# PAYL0005_PC_Microcontroller_Power.net
KiCad netlist of a schematic drawn in Altium Designer
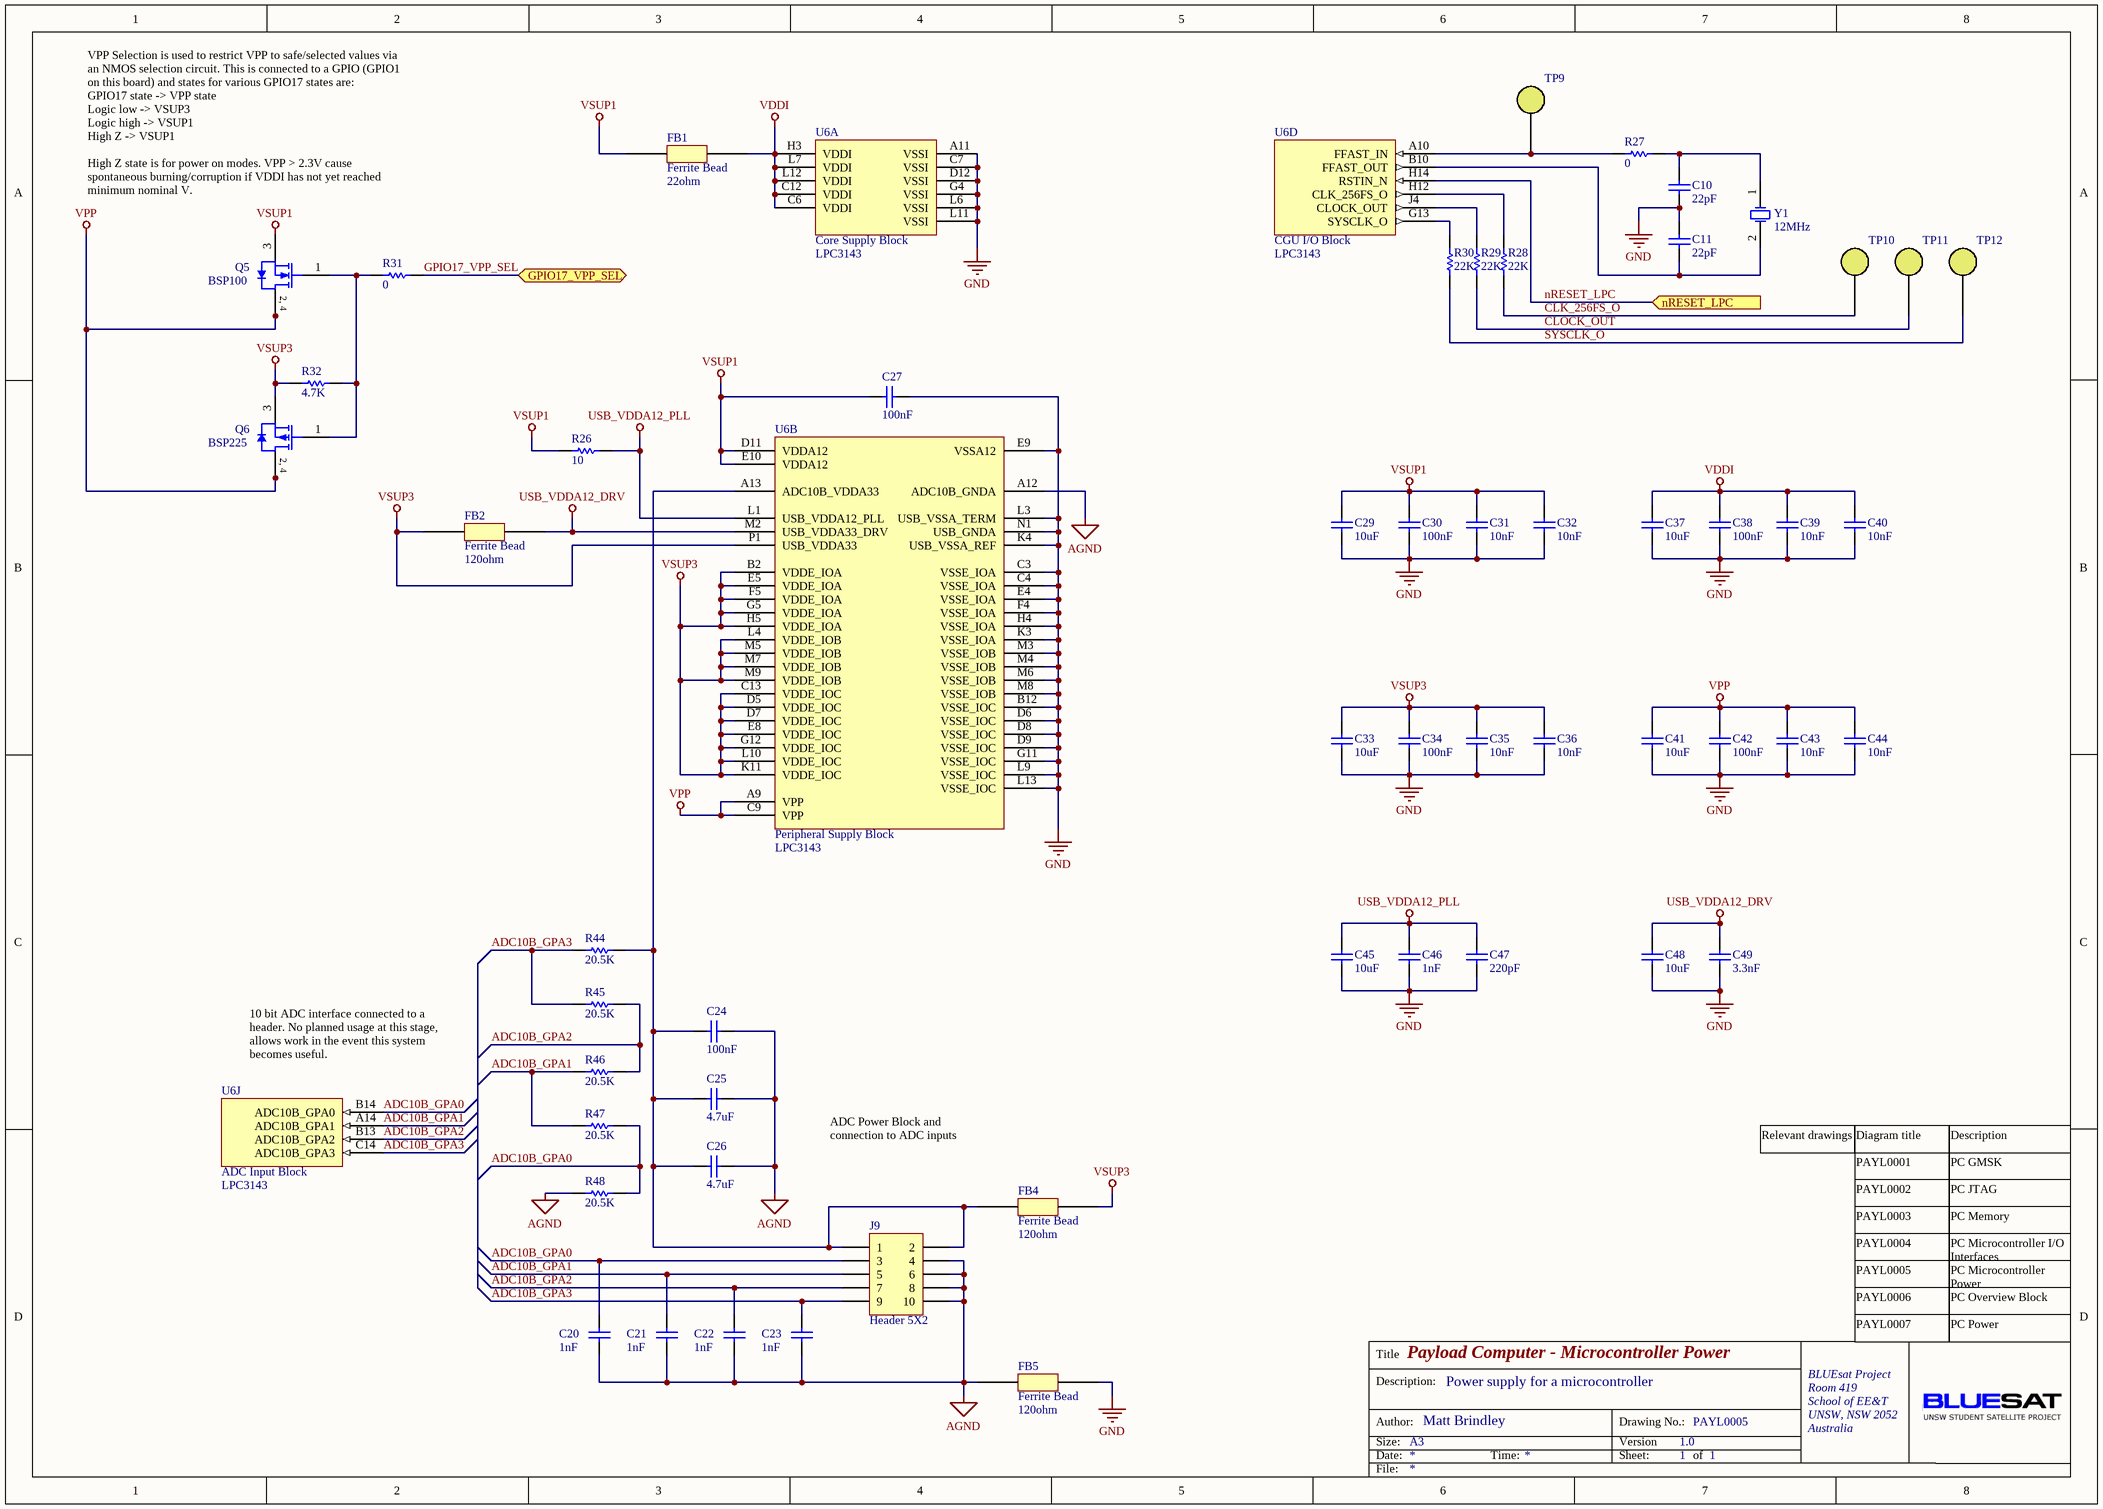
[diagram p0: PAYL0005_PC_Microcontroller_Power.SchDoc]

(export (version "E")
  (design (tool "Eeschema 10.0.6"))
  (components
    (comp (ref "C10")
      (value "22pF")
      (footprint "C0805")
      (description "Capacitor (Semiconductor SIM Model)")
      (fields (field (name "Comment") "Cap Semi") (field (name "PUBLISHER") "Altium Limited"))
      (libsource (lib "Miscellaneous Devices") (part "Cap Semi"))
    )
    (comp (ref "C11")
      (value "22pF")
      (footprint "C0805")
      (description "Capacitor (Semiconductor SIM Model)")
      (fields (field (name "Comment") "Cap Semi") (field (name "PUBLISHER") "Altium Limited"))
      (libsource (lib "Miscellaneous Devices") (part "Cap Semi"))
    )
    (comp (ref "C20")
      (value "1nF")
      (footprint "C0805")
      (description "Capacitor (Semiconductor SIM Model)")
      (fields (field (name "Comment") "Cap Semi") (field (name "PUBLISHER") "Altium Limited"))
      (libsource (lib "Miscellaneous Devices") (part "Cap Semi"))
    )
    (comp (ref "C21")
      (value "1nF")
      (footprint "C0805")
      (description "Capacitor (Semiconductor SIM Model)")
      (fields (field (name "Comment") "Cap Semi") (field (name "PUBLISHER") "Altium Limited"))
      (libsource (lib "Miscellaneous Devices") (part "Cap Semi"))
    )
    (comp (ref "C22")
      (value "1nF")
      (footprint "C0805")
      (description "Capacitor (Semiconductor SIM Model)")
      (fields (field (name "Comment") "Cap Semi") (field (name "PUBLISHER") "Altium Limited"))
      (libsource (lib "Miscellaneous Devices") (part "Cap Semi"))
    )
    (comp (ref "C23")
      (value "1nF")
      (footprint "C0805")
      (description "Capacitor (Semiconductor SIM Model)")
      (fields (field (name "Comment") "Cap Semi") (field (name "PUBLISHER") "Altium Limited"))
      (libsource (lib "Miscellaneous Devices") (part "Cap Semi"))
    )
    (comp (ref "C24")
      (value "100nF")
      (footprint "C0805")
      (description "Capacitor (Semiconductor SIM Model)")
      (fields (field (name "Comment") "Cap Semi") (field (name "PUBLISHER") "Altium Limited"))
      (libsource (lib "Miscellaneous Devices") (part "Cap Semi"))
    )
    (comp (ref "C25")
      (value "4.7uF")
      (footprint "C0805")
      (description "Capacitor (Semiconductor SIM Model)")
      (fields (field (name "Comment") "Cap Semi") (field (name "PUBLISHER") "Altium Limited"))
      (libsource (lib "Miscellaneous Devices") (part "Cap Semi"))
    )
    (comp (ref "C26")
      (value "4.7uF")
      (footprint "C0805")
      (description "Capacitor (Semiconductor SIM Model)")
      (fields (field (name "Comment") "Cap Semi") (field (name "PUBLISHER") "Altium Limited"))
      (libsource (lib "Miscellaneous Devices") (part "Cap Semi"))
    )
    (comp (ref "C27")
      (value "100nF")
      (footprint "C0805")
      (description "Capacitor (Semiconductor SIM Model)")
      (fields (field (name "Comment") "Cap Semi") (field (name "PUBLISHER") "Altium Limited"))
      (libsource (lib "Miscellaneous Devices") (part "Cap Semi"))
    )
    (comp (ref "C29")
      (value "10uF")
      (footprint "C0805")
      (description "Capacitor (Semiconductor SIM Model)")
      (fields (field (name "Comment") "Cap Semi") (field (name "PUBLISHER") "Altium Limited"))
      (libsource (lib "Miscellaneous Devices") (part "Cap Semi"))
    )
    (comp (ref "C30")
      (value "100nF")
      (footprint "C0805")
      (description "Capacitor (Semiconductor SIM Model)")
      (fields (field (name "Comment") "Cap Semi") (field (name "PUBLISHER") "Altium Limited"))
      (libsource (lib "Miscellaneous Devices") (part "Cap Semi"))
    )
    (comp (ref "C31")
      (value "10nF")
      (footprint "C0805")
      (description "Capacitor (Semiconductor SIM Model)")
      (fields (field (name "Comment") "Cap Semi") (field (name "PUBLISHER") "Altium Limited"))
      (libsource (lib "Miscellaneous Devices") (part "Cap Semi"))
    )
    (comp (ref "C32")
      (value "10nF")
      (footprint "C0805")
      (description "Capacitor (Semiconductor SIM Model)")
      (fields (field (name "Comment") "Cap Semi") (field (name "PUBLISHER") "Altium Limited"))
      (libsource (lib "Miscellaneous Devices") (part "Cap Semi"))
    )
    (comp (ref "C33")
      (value "10uF")
      (footprint "C0805")
      (description "Capacitor (Semiconductor SIM Model)")
      (fields (field (name "Comment") "Cap Semi") (field (name "PUBLISHER") "Altium Limited"))
      (libsource (lib "Miscellaneous Devices") (part "Cap Semi"))
    )
    (comp (ref "C34")
      (value "100nF")
      (footprint "C0805")
      (description "Capacitor (Semiconductor SIM Model)")
      (fields (field (name "Comment") "Cap Semi") (field (name "PUBLISHER") "Altium Limited"))
      (libsource (lib "Miscellaneous Devices") (part "Cap Semi"))
    )
    (comp (ref "C35")
      (value "10nF")
      (footprint "C0805")
      (description "Capacitor (Semiconductor SIM Model)")
      (fields (field (name "Comment") "Cap Semi") (field (name "PUBLISHER") "Altium Limited"))
      (libsource (lib "Miscellaneous Devices") (part "Cap Semi"))
    )
    (comp (ref "C36")
      (value "10nF")
      (footprint "C0805")
      (description "Capacitor (Semiconductor SIM Model)")
      (fields (field (name "Comment") "Cap Semi") (field (name "PUBLISHER") "Altium Limited"))
      (libsource (lib "Miscellaneous Devices") (part "Cap Semi"))
    )
    (comp (ref "C37")
      (value "10uF")
      (footprint "C0805")
      (description "Capacitor (Semiconductor SIM Model)")
      (fields (field (name "Comment") "Cap Semi") (field (name "PUBLISHER") "Altium Limited"))
      (libsource (lib "Miscellaneous Devices") (part "Cap Semi"))
    )
    (comp (ref "C38")
      (value "100nF")
      (footprint "C0805")
      (description "Capacitor (Semiconductor SIM Model)")
      (fields (field (name "Comment") "Cap Semi") (field (name "PUBLISHER") "Altium Limited"))
      (libsource (lib "Miscellaneous Devices") (part "Cap Semi"))
    )
    (comp (ref "C39")
      (value "10nF")
      (footprint "C0805")
      (description "Capacitor (Semiconductor SIM Model)")
      (fields (field (name "Comment") "Cap Semi") (field (name "PUBLISHER") "Altium Limited"))
      (libsource (lib "Miscellaneous Devices") (part "Cap Semi"))
    )
    (comp (ref "C40")
      (value "10nF")
      (footprint "C0805")
      (description "Capacitor (Semiconductor SIM Model)")
      (fields (field (name "Comment") "Cap Semi") (field (name "PUBLISHER") "Altium Limited"))
      (libsource (lib "Miscellaneous Devices") (part "Cap Semi"))
    )
    (comp (ref "C41")
      (value "10uF")
      (footprint "C0805")
      (description "Capacitor (Semiconductor SIM Model)")
      (fields (field (name "Comment") "Cap Semi") (field (name "PUBLISHER") "Altium Limited"))
      (libsource (lib "Miscellaneous Devices") (part "Cap Semi"))
    )
    (comp (ref "C42")
      (value "100nF")
      (footprint "C0805")
      (description "Capacitor (Semiconductor SIM Model)")
      (fields (field (name "Comment") "Cap Semi") (field (name "PUBLISHER") "Altium Limited"))
      (libsource (lib "Miscellaneous Devices") (part "Cap Semi"))
    )
    (comp (ref "C43")
      (value "10nF")
      (footprint "C0805")
      (description "Capacitor (Semiconductor SIM Model)")
      (fields (field (name "Comment") "Cap Semi") (field (name "PUBLISHER") "Altium Limited"))
      (libsource (lib "Miscellaneous Devices") (part "Cap Semi"))
    )
    (comp (ref "C44")
      (value "10nF")
      (footprint "C0805")
      (description "Capacitor (Semiconductor SIM Model)")
      (fields (field (name "Comment") "Cap Semi") (field (name "PUBLISHER") "Altium Limited"))
      (libsource (lib "Miscellaneous Devices") (part "Cap Semi"))
    )
    (comp (ref "C45")
      (value "10uF")
      (footprint "C0805")
      (description "Capacitor (Semiconductor SIM Model)")
      (fields (field (name "Comment") "Cap Semi") (field (name "PUBLISHER") "Altium Limited"))
      (libsource (lib "Miscellaneous Devices") (part "Cap Semi"))
    )
    (comp (ref "C46")
      (value "1nF")
      (footprint "C0805")
      (description "Capacitor (Semiconductor SIM Model)")
      (fields (field (name "Comment") "Cap Semi") (field (name "PUBLISHER") "Altium Limited"))
      (libsource (lib "Miscellaneous Devices") (part "Cap Semi"))
    )
    (comp (ref "C47")
      (value "220pF")
      (footprint "C0805")
      (description "Capacitor (Semiconductor SIM Model)")
      (fields (field (name "Comment") "Cap Semi") (field (name "PUBLISHER") "Altium Limited"))
      (libsource (lib "Miscellaneous Devices") (part "Cap Semi"))
    )
    (comp (ref "C48")
      (value "10uF")
      (footprint "C0805")
      (description "Capacitor (Semiconductor SIM Model)")
      (fields (field (name "Comment") "Cap Semi") (field (name "PUBLISHER") "Altium Limited"))
      (libsource (lib "Miscellaneous Devices") (part "Cap Semi"))
    )
    (comp (ref "C49")
      (value "3.3nF")
      (footprint "C0805")
      (description "Capacitor (Semiconductor SIM Model)")
      (fields (field (name "Comment") "Cap Semi") (field (name "PUBLISHER") "Altium Limited"))
      (libsource (lib "Miscellaneous Devices") (part "Cap Semi"))
    )
    (comp (ref "FB1")
      (value "Ferrite Bead")
      (footprint "AXIAL-0.3")
      (description "Standard Ferrite Bead")
      (fields (field (name "ALTIUM_VALUE") "22ohm") (field (name "PUBLISHER") "Altium Limited"))
      (libsource (lib "PC_Components") (part "Ferrite Bead"))
    )
    (comp (ref "FB2")
      (value "Ferrite Bead")
      (footprint "AXIAL-0.3")
      (description "Standard Ferrite Bead")
      (fields (field (name "ALTIUM_VALUE") "120ohm") (field (name "PUBLISHER") "Altium Limited"))
      (libsource (lib "PC_Components") (part "Ferrite Bead"))
    )
    (comp (ref "FB4")
      (value "Ferrite Bead")
      (footprint "AXIAL-0.3")
      (description "Standard Ferrite Bead")
      (fields (field (name "ALTIUM_VALUE") "120ohm") (field (name "PUBLISHER") "Altium Limited"))
      (libsource (lib "PC_Components") (part "Ferrite Bead"))
    )
    (comp (ref "FB5")
      (value "Ferrite Bead")
      (footprint "AXIAL-0.3")
      (description "Standard Ferrite Bead")
      (fields (field (name "ALTIUM_VALUE") "120ohm") (field (name "PUBLISHER") "Altium Limited"))
      (libsource (lib "PC_Components") (part "Ferrite Bead"))
    )
    (comp (ref "J9")
      (value "Header 5X2")
      (footprint "HDR2X5")
      (description "Header, 5-Pin, Dual row")
      (fields (field (name "PUBLISHER") "Altium Limited"))
      (libsource (lib "Miscellaneous Connectors") (part "Header 5X2"))
    )
    (comp (ref "Q5")
      (value "BSP100")
      (footprint "SOT223_N")
      (description "N-channel Enhancement Mode MOSFET")
      (fields (field (name "PUBLISHER") "Altium Limited"))
      (libsource (lib "Philips Discrete MOSFET - Power") (part "BSP100"))
    )
    (comp (ref "Q6")
      (value "BSP225")
      (footprint "SOT223_N")
      (description "P-channel Enhancement Mode Vertical D-MOSFET")
      (fields (field (name "PUBLISHER") "Altium Limited"))
      (libsource (lib "Philips Discrete MOSFET - Power") (part "BSP225"))
    )
    (comp (ref "R26")
      (value "10")
      (footprint "6-0805_L")
      (description "Semiconductor Resistor")
      (fields (field (name "Comment") "Res Semi") (field (name "PUBLISHER") "Altium Limited"))
      (libsource (lib "Miscellaneous Devices") (part "Res Semi"))
    )
    (comp (ref "R27")
      (value "0")
      (footprint "6-0805_L")
      (description "Semiconductor Resistor")
      (fields (field (name "Comment") "Res Semi") (field (name "PUBLISHER") "Altium Limited"))
      (libsource (lib "Miscellaneous Devices") (part "Res Semi"))
    )
    (comp (ref "R28")
      (value "22K")
      (footprint "6-0805_L")
      (description "Semiconductor Resistor")
      (fields (field (name "Comment") "Res Semi") (field (name "PUBLISHER") "Altium Limited"))
      (libsource (lib "Miscellaneous Devices") (part "Res Semi"))
    )
    (comp (ref "R29")
      (value "22K")
      (footprint "6-0805_L")
      (description "Semiconductor Resistor")
      (fields (field (name "Comment") "Res Semi") (field (name "PUBLISHER") "Altium Limited"))
      (libsource (lib "Miscellaneous Devices") (part "Res Semi"))
    )
    (comp (ref "R30")
      (value "22K")
      (footprint "6-0805_L")
      (description "Semiconductor Resistor")
      (fields (field (name "Comment") "Res Semi") (field (name "PUBLISHER") "Altium Limited"))
      (libsource (lib "Miscellaneous Devices") (part "Res Semi"))
    )
    (comp (ref "R31")
      (value "0")
      (footprint "6-0805_L")
      (description "Semiconductor Resistor")
      (fields (field (name "Comment") "Res Semi") (field (name "PUBLISHER") "Altium Limited"))
      (libsource (lib "Miscellaneous Devices") (part "Res Semi"))
    )
    (comp (ref "R32")
      (value "4.7K")
      (footprint "6-0805_L")
      (description "Semiconductor Resistor")
      (fields (field (name "Comment") "Res Semi") (field (name "PUBLISHER") "Altium Limited"))
      (libsource (lib "Miscellaneous Devices") (part "Res Semi"))
    )
    (comp (ref "R44")
      (value "20.5K")
      (footprint "6-0805_L")
      (description "Semiconductor Resistor")
      (fields (field (name "Comment") "Res Semi") (field (name "PUBLISHER") "Altium Limited"))
      (libsource (lib "Miscellaneous Devices") (part "Res Semi"))
    )
    (comp (ref "R45")
      (value "20.5K")
      (footprint "6-0805_L")
      (description "Semiconductor Resistor")
      (fields (field (name "Comment") "Res Semi") (field (name "PUBLISHER") "Altium Limited"))
      (libsource (lib "Miscellaneous Devices") (part "Res Semi"))
    )
    (comp (ref "R46")
      (value "20.5K")
      (footprint "6-0805_L")
      (description "Semiconductor Resistor")
      (fields (field (name "Comment") "Res Semi") (field (name "PUBLISHER") "Altium Limited"))
      (libsource (lib "Miscellaneous Devices") (part "Res Semi"))
    )
    (comp (ref "R47")
      (value "20.5K")
      (footprint "6-0805_L")
      (description "Semiconductor Resistor")
      (fields (field (name "Comment") "Res Semi") (field (name "PUBLISHER") "Altium Limited"))
      (libsource (lib "Miscellaneous Devices") (part "Res Semi"))
    )
    (comp (ref "R48")
      (value "20.5K")
      (footprint "6-0805_L")
      (description "Semiconductor Resistor")
      (fields (field (name "Comment") "Res Semi") (field (name "PUBLISHER") "Altium Limited"))
      (libsource (lib "Miscellaneous Devices") (part "Res Semi"))
    )
    (comp (ref "TP9")
      (value "Test Point")
      (footprint "PIN1")
      (description "Test point")
      (fields (field (name "PUBLISHER") "Altium Limited"))
      (libsource (lib "PC_Components") (part "Test Point"))
    )
    (comp (ref "TP10")
      (value "Test Point")
      (footprint "PIN1")
      (description "Test point")
      (fields (field (name "PUBLISHER") "Altium Limited"))
      (libsource (lib "PC_Components") (part "Test Point"))
    )
    (comp (ref "TP11")
      (value "Test Point")
      (footprint "PIN1")
      (description "Test point")
      (fields (field (name "PUBLISHER") "Altium Limited"))
      (libsource (lib "PC_Components") (part "Test Point"))
    )
    (comp (ref "TP12")
      (value "Test Point")
      (footprint "PIN1")
      (description "Test point")
      (fields (field (name "PUBLISHER") "Altium Limited"))
      (libsource (lib "PC_Components") (part "Test Point"))
    )
    (comp (ref "U6")
      (value "LPC3143")
      (footprint "PC_Footprints:BGA180C80P14X14_1200X1200X120")
      (description "NXP ARM9 based microcontroller")
      (fields (field (name "PUBLISHER") "BLUEsat Project"))
      (libsource (lib "PC_Components") (part "LPC3143"))
    )
    (comp (ref "Y1")
      (value "12MHz")
      (footprint "RAD-0.3")
      (description "Crystal Oscillator")
      (fields (field (name "Comment") "XTAL") (field (name "PUBLISHER") "Altium Limited"))
      (libsource (lib "Miscellaneous Devices") (part "XTAL"))
    )
  )
  (nets
    (net (code "1") (name "/ADC10B_GPA0") (class "Default")
      (node (ref "C20") (pin "2") (pinfunction "2_2") (pintype "passive"))
      (node (ref "J9") (pin "3") (pinfunction "3_3") (pintype "passive"))
      (node (ref "R47") (pin "2") (pinfunction "2_2") (pintype "passive"))
      (node (ref "R48") (pin "2") (pinfunction "2_2") (pintype "passive"))
      (node (ref "U6") (pin "B14") (pinfunction "ADC10B_GPA0_B14") (pintype "input"))
    )
    (net (code "2") (name "/ADC10B_GPA1") (class "Default")
      (node (ref "C21") (pin "2") (pinfunction "2_2") (pintype "passive"))
      (node (ref "J9") (pin "5") (pinfunction "5_5") (pintype "passive"))
      (node (ref "R46") (pin "1") (pinfunction "1_1") (pintype "passive"))
      (node (ref "R47") (pin "1") (pinfunction "1_1") (pintype "passive"))
      (node (ref "U6") (pin "A14") (pinfunction "ADC10B_GPA1_A14") (pintype "input"))
    )
    (net (code "3") (name "/ADC10B_GPA2") (class "Default")
      (node (ref "C22") (pin "2") (pinfunction "2_2") (pintype "passive"))
      (node (ref "J9") (pin "7") (pinfunction "7_7") (pintype "passive"))
      (node (ref "R45") (pin "2") (pinfunction "2_2") (pintype "passive"))
      (node (ref "R46") (pin "2") (pinfunction "2_2") (pintype "passive"))
      (node (ref "U6") (pin "B13") (pinfunction "ADC10B_GPA2_B13") (pintype "input"))
    )
    (net (code "4") (name "/ADC10B_GPA3") (class "Default")
      (node (ref "C23") (pin "2") (pinfunction "2_2") (pintype "passive"))
      (node (ref "J9") (pin "9") (pinfunction "9_9") (pintype "passive"))
      (node (ref "R44") (pin "1") (pinfunction "1_1") (pintype "passive"))
      (node (ref "R45") (pin "1") (pinfunction "1_1") (pintype "passive"))
      (node (ref "U6") (pin "C14") (pinfunction "ADC10B_GPA3_C14") (pintype "input"))
    )
    (net (code "5") (name "/CLK_256FS_O") (class "Default")
      (node (ref "R28") (pin "1") (pinfunction "1_1") (pintype "passive"))
      (node (ref "TP10") (pin "1") (pinfunction "1_1") (pintype "passive"))
    )
    (net (code "6") (name "/CLOCK_OUT") (class "Default")
      (node (ref "R29") (pin "1") (pinfunction "1_1") (pintype "passive"))
      (node (ref "TP11") (pin "1") (pinfunction "1_1") (pintype "passive"))
    )
    (net (code "7") (name "/GPIO17_VPP_SEL") (class "Default")
      (node (ref "R31") (pin "2") (pinfunction "2_2") (pintype "passive"))
    )
    (net (code "8") (name "/SYSCLK_O") (class "Default")
      (node (ref "R30") (pin "1") (pinfunction "1_1") (pintype "passive"))
      (node (ref "TP12") (pin "1") (pinfunction "1_1") (pintype "passive"))
    )
    (net (code "9") (name "/nRESET_LPC") (class "Default")
      (node (ref "U6") (pin "H14") (pinfunction "RSTIN_N_H14") (pintype "input"))
    )
    (net (code "10") (name "AGND") (class "Default")
      (node (ref "C20") (pin "1") (pinfunction "1_1") (pintype "passive"))
      (node (ref "C21") (pin "1") (pinfunction "1_1") (pintype "passive"))
      (node (ref "C22") (pin "1") (pinfunction "1_1") (pintype "passive"))
      (node (ref "C23") (pin "1") (pinfunction "1_1") (pintype "passive"))
      (node (ref "C24") (pin "1") (pinfunction "1_1") (pintype "passive"))
      (node (ref "C25") (pin "1") (pinfunction "1_1") (pintype "passive"))
      (node (ref "C26") (pin "1") (pinfunction "1_1") (pintype "passive"))
      (node (ref "FB5") (pin "2") (pinfunction "2_2") (pintype "passive"))
      (node (ref "J9") (pin "10") (pinfunction "10_10") (pintype "passive"))
      (node (ref "J9") (pin "4") (pinfunction "4_4") (pintype "passive"))
      (node (ref "J9") (pin "6") (pinfunction "6_6") (pintype "passive"))
      (node (ref "J9") (pin "8") (pinfunction "8_8") (pintype "passive"))
      (node (ref "R48") (pin "1") (pinfunction "1_1") (pintype "passive"))
      (node (ref "U6") (pin "A12") (pinfunction "ADC10B_GNDA_A12") (pintype "power_in"))
    )
    (net (code "11") (name "GND") (class "Default")
      (node (ref "C10") (pin "2") (pinfunction "2_2") (pintype "passive"))
      (node (ref "C11") (pin "1") (pinfunction "1_1") (pintype "passive"))
      (node (ref "C27") (pin "1") (pinfunction "1_1") (pintype "passive"))
      (node (ref "C29") (pin "2") (pinfunction "2_2") (pintype "passive"))
      (node (ref "C30") (pin "2") (pinfunction "2_2") (pintype "passive"))
      (node (ref "C31") (pin "2") (pinfunction "2_2") (pintype "passive"))
      (node (ref "C32") (pin "2") (pinfunction "2_2") (pintype "passive"))
      (node (ref "C33") (pin "2") (pinfunction "2_2") (pintype "passive"))
      (node (ref "C34") (pin "2") (pinfunction "2_2") (pintype "passive"))
      (node (ref "C35") (pin "2") (pinfunction "2_2") (pintype "passive"))
      (node (ref "C36") (pin "2") (pinfunction "2_2") (pintype "passive"))
      (node (ref "C37") (pin "2") (pinfunction "2_2") (pintype "passive"))
      (node (ref "C38") (pin "2") (pinfunction "2_2") (pintype "passive"))
      (node (ref "C39") (pin "2") (pinfunction "2_2") (pintype "passive"))
      (node (ref "C40") (pin "2") (pinfunction "2_2") (pintype "passive"))
      (node (ref "C41") (pin "2") (pinfunction "2_2") (pintype "passive"))
      (node (ref "C42") (pin "2") (pinfunction "2_2") (pintype "passive"))
      (node (ref "C43") (pin "2") (pinfunction "2_2") (pintype "passive"))
      (node (ref "C44") (pin "2") (pinfunction "2_2") (pintype "passive"))
      (node (ref "C45") (pin "2") (pinfunction "2_2") (pintype "passive"))
      (node (ref "C46") (pin "2") (pinfunction "2_2") (pintype "passive"))
      (node (ref "C47") (pin "2") (pinfunction "2_2") (pintype "passive"))
      (node (ref "C48") (pin "2") (pinfunction "2_2") (pintype "passive"))
      (node (ref "C49") (pin "2") (pinfunction "2_2") (pintype "passive"))
      (node (ref "FB5") (pin "1") (pinfunction "1_1") (pintype "passive"))
      (node (ref "U6") (pin "A11") (pinfunction "VSSI_A11") (pintype "power_in"))
      (node (ref "U6") (pin "B12") (pinfunction "VSSE_IOC_B12") (pintype "power_in"))
      (node (ref "U6") (pin "C3") (pinfunction "VSSE_IOA_C3") (pintype "power_in"))
      (node (ref "U6") (pin "C4") (pinfunction "VSSE_IOA_C4") (pintype "power_in"))
      (node (ref "U6") (pin "C7") (pinfunction "VSSI_C7") (pintype "power_in"))
      (node (ref "U6") (pin "D12") (pinfunction "VSSI_D12") (pintype "power_in"))
      (node (ref "U6") (pin "D6") (pinfunction "VSSE_IOC_D6") (pintype "power_in"))
      (node (ref "U6") (pin "D8") (pinfunction "VSSE_IOC_D8") (pintype "power_in"))
      (node (ref "U6") (pin "D9") (pinfunction "VSSE_IOC_D9") (pintype "power_in"))
      (node (ref "U6") (pin "E4") (pinfunction "VSSE_IOA_E4") (pintype "power_in"))
      (node (ref "U6") (pin "E9") (pinfunction "VSSA12_E9") (pintype "power_in"))
      (node (ref "U6") (pin "F4") (pinfunction "VSSE_IOA_F4") (pintype "power_in"))
      (node (ref "U6") (pin "G11") (pinfunction "VSSE_IOC_G11") (pintype "power_in"))
      (node (ref "U6") (pin "G4") (pinfunction "VSSI_G4") (pintype "power_in"))
      (node (ref "U6") (pin "H4") (pinfunction "VSSE_IOA_H4") (pintype "power_in"))
      (node (ref "U6") (pin "K3") (pinfunction "VSSE_IOA_K3") (pintype "power_in"))
      (node (ref "U6") (pin "K4") (pinfunction "USB_VSSA_REF_K4") (pintype "power_in"))
      (node (ref "U6") (pin "L11") (pinfunction "VSSI_L11") (pintype "power_in"))
      (node (ref "U6") (pin "L13") (pinfunction "VSSE_IOC_L13") (pintype "power_in"))
      (node (ref "U6") (pin "L3") (pinfunction "USB_VSSA_TERM_L3") (pintype "power_in"))
      (node (ref "U6") (pin "L6") (pinfunction "VSSI_L6") (pintype "power_in"))
      (node (ref "U6") (pin "L9") (pinfunction "VSSE_IOC_L9") (pintype "power_in"))
      (node (ref "U6") (pin "M3") (pinfunction "VSSE_IOB_M3") (pintype "power_in"))
      (node (ref "U6") (pin "M4") (pinfunction "VSSE_IOB_M4") (pintype "power_in"))
      (node (ref "U6") (pin "M6") (pinfunction "VSSE_IOB_M6") (pintype "power_in"))
      (node (ref "U6") (pin "M8") (pinfunction "VSSE_IOB_M8") (pintype "power_in"))
      (node (ref "U6") (pin "N1") (pinfunction "USB_GNDA_N1") (pintype "power_in"))
    )
    (net (code "12") (name "Net-(Q5-G)") (class "Default")
      (node (ref "Q5") (pin "1") (pinfunction "G_1") (pintype "passive"))
      (node (ref "Q6") (pin "1") (pinfunction "G_1") (pintype "passive"))
      (node (ref "R31") (pin "1") (pinfunction "1_1") (pintype "passive"))
      (node (ref "R32") (pin "2") (pinfunction "2_2") (pintype "passive"))
    )
    (net (code "13") (name "Net-(U6B-ADC10B_VDDA33)") (class "Default")
      (node (ref "C24") (pin "2") (pinfunction "2_2") (pintype "passive"))
      (node (ref "C25") (pin "2") (pinfunction "2_2") (pintype "passive"))
      (node (ref "C26") (pin "2") (pinfunction "2_2") (pintype "passive"))
      (node (ref "FB4") (pin "2") (pinfunction "2_2") (pintype "passive"))
      (node (ref "J9") (pin "1") (pinfunction "1_1") (pintype "passive"))
      (node (ref "J9") (pin "2") (pinfunction "2_2") (pintype "passive"))
      (node (ref "R44") (pin "2") (pinfunction "2_2") (pintype "passive"))
      (node (ref "U6") (pin "A13") (pinfunction "ADC10B_VDDA33_A13") (pintype "power_in"))
    )
    (net (code "14") (name "Net-(U6D-CLK_256FS_O)") (class "Default")
      (node (ref "R28") (pin "2") (pinfunction "2_2") (pintype "passive"))
      (node (ref "U6") (pin "H12") (pinfunction "CLK_256FS_O_H12") (pintype "output"))
    )
    (net (code "15") (name "Net-(U6D-CLOCK_OUT)") (class "Default")
      (node (ref "R29") (pin "2") (pinfunction "2_2") (pintype "passive"))
      (node (ref "U6") (pin "J4") (pinfunction "CLOCK_OUT_J4") (pintype "output"))
    )
    (net (code "16") (name "Net-(U6D-FFAST_IN)") (class "Default")
      (node (ref "R27") (pin "1") (pinfunction "1_1") (pintype "passive"))
      (node (ref "TP9") (pin "1") (pinfunction "1_1") (pintype "passive"))
      (node (ref "U6") (pin "A10") (pinfunction "FFAST_IN_A10") (pintype "input"))
    )
    (net (code "17") (name "Net-(U6D-FFAST_OUT)") (class "Default")
      (node (ref "C11") (pin "2") (pinfunction "2_2") (pintype "passive"))
      (node (ref "U6") (pin "B10") (pinfunction "FFAST_OUT_B10") (pintype "output"))
      (node (ref "Y1") (pin "2") (pinfunction "OSC2_2") (pintype "passive"))
    )
    (net (code "18") (name "Net-(U6D-SYSCLK_O)") (class "Default")
      (node (ref "R30") (pin "2") (pinfunction "2_2") (pintype "passive"))
      (node (ref "U6") (pin "G13") (pinfunction "SYSCLK_O_G13") (pintype "output"))
    )
    (net (code "19") (name "Net-(Y1-OSC1)") (class "Default")
      (node (ref "C10") (pin "1") (pinfunction "1_1") (pintype "passive"))
      (node (ref "R27") (pin "2") (pinfunction "2_2") (pintype "passive"))
      (node (ref "Y1") (pin "1") (pinfunction "OSC1_1") (pintype "passive"))
    )
    (net (code "20") (name "USB_VDDA12_DRV") (class "Default")
      (node (ref "C48") (pin "1") (pinfunction "1_1") (pintype "passive"))
      (node (ref "C49") (pin "1") (pinfunction "1_1") (pintype "passive"))
      (node (ref "FB2") (pin "1") (pinfunction "1_1") (pintype "passive"))
      (node (ref "U6") (pin "M2") (pinfunction "USB_VDDA33_DRV_M2") (pintype "power_in"))
    )
    (net (code "21") (name "USB_VDDA12_PLL") (class "Default")
      (node (ref "C45") (pin "1") (pinfunction "1_1") (pintype "passive"))
      (node (ref "C46") (pin "1") (pinfunction "1_1") (pintype "passive"))
      (node (ref "C47") (pin "1") (pinfunction "1_1") (pintype "passive"))
      (node (ref "R26") (pin "2") (pinfunction "2_2") (pintype "passive"))
      (node (ref "U6") (pin "L1") (pinfunction "USB_VDDA12_PLL_L1") (pintype "power_in"))
    )
    (net (code "22") (name "VDDI") (class "Default")
      (node (ref "C37") (pin "1") (pinfunction "1_1") (pintype "passive"))
      (node (ref "C38") (pin "1") (pinfunction "1_1") (pintype "passive"))
      (node (ref "C39") (pin "1") (pinfunction "1_1") (pintype "passive"))
      (node (ref "C40") (pin "1") (pinfunction "1_1") (pintype "passive"))
      (node (ref "FB1") (pin "1") (pinfunction "1_1") (pintype "passive"))
      (node (ref "U6") (pin "C12") (pinfunction "VDDI_C12") (pintype "power_in"))
      (node (ref "U6") (pin "C6") (pinfunction "VDDI_C6") (pintype "power_in"))
      (node (ref "U6") (pin "H3") (pinfunction "VDDI_H3") (pintype "power_in"))
      (node (ref "U6") (pin "L12") (pinfunction "VDDI_L12") (pintype "power_in"))
      (node (ref "U6") (pin "L7") (pinfunction "VDDI_L7") (pintype "power_in"))
    )
    (net (code "23") (name "VPP") (class "Default")
      (node (ref "C41") (pin "1") (pinfunction "1_1") (pintype "passive"))
      (node (ref "C42") (pin "1") (pinfunction "1_1") (pintype "passive"))
      (node (ref "C43") (pin "1") (pinfunction "1_1") (pintype "passive"))
      (node (ref "C44") (pin "1") (pinfunction "1_1") (pintype "passive"))
      (node (ref "Q5") (pin "2") (pinfunction "D_2") (pintype "passive"))
      (node (ref "Q5") (pin "4") (pinfunction "D_4") (pintype "passive"))
      (node (ref "Q6") (pin "2") (pinfunction "D_2") (pintype "passive"))
      (node (ref "Q6") (pin "4") (pinfunction "D_4") (pintype "passive"))
      (node (ref "U6") (pin "A9") (pinfunction "VPP_A9") (pintype "power_in"))
      (node (ref "U6") (pin "C9") (pinfunction "VPP_C9") (pintype "power_in"))
    )
    (net (code "24") (name "VSUP1") (class "Default")
      (node (ref "C27") (pin "2") (pinfunction "2_2") (pintype "passive"))
      (node (ref "C29") (pin "1") (pinfunction "1_1") (pintype "passive"))
      (node (ref "C30") (pin "1") (pinfunction "1_1") (pintype "passive"))
      (node (ref "C31") (pin "1") (pinfunction "1_1") (pintype "passive"))
      (node (ref "C32") (pin "1") (pinfunction "1_1") (pintype "passive"))
      (node (ref "FB1") (pin "2") (pinfunction "2_2") (pintype "passive"))
      (node (ref "Q5") (pin "3") (pinfunction "S_3") (pintype "passive"))
      (node (ref "R26") (pin "1") (pinfunction "1_1") (pintype "passive"))
      (node (ref "U6") (pin "D11") (pinfunction "VDDA12_D11") (pintype "power_in"))
      (node (ref "U6") (pin "E10") (pinfunction "VDDA12_E10") (pintype "power_in"))
    )
    (net (code "25") (name "VSUP3") (class "Default")
      (node (ref "C33") (pin "1") (pinfunction "1_1") (pintype "passive"))
      (node (ref "C34") (pin "1") (pinfunction "1_1") (pintype "passive"))
      (node (ref "C35") (pin "1") (pinfunction "1_1") (pintype "passive"))
      (node (ref "C36") (pin "1") (pinfunction "1_1") (pintype "passive"))
      (node (ref "FB2") (pin "2") (pinfunction "2_2") (pintype "passive"))
      (node (ref "FB4") (pin "1") (pinfunction "1_1") (pintype "passive"))
      (node (ref "Q6") (pin "3") (pinfunction "S_3") (pintype "passive"))
      (node (ref "R32") (pin "1") (pinfunction "1_1") (pintype "passive"))
      (node (ref "U6") (pin "B2") (pinfunction "VDDE_IOA_B2") (pintype "power_in"))
      (node (ref "U6") (pin "C13") (pinfunction "VDDE_IOC_C13") (pintype "power_in"))
      (node (ref "U6") (pin "D5") (pinfunction "VDDE_IOC_D5") (pintype "power_in"))
      (node (ref "U6") (pin "D7") (pinfunction "VDDE_IOC_D7") (pintype "power_in"))
      (node (ref "U6") (pin "E5") (pinfunction "VDDE_IOA_E5") (pintype "power_in"))
      (node (ref "U6") (pin "E8") (pinfunction "VDDE_IOC_E8") (pintype "power_in"))
      (node (ref "U6") (pin "F5") (pinfunction "VDDE_IOA_F5") (pintype "power_in"))
      (node (ref "U6") (pin "G12") (pinfunction "VDDE_IOC_G12") (pintype "power_in"))
      (node (ref "U6") (pin "G5") (pinfunction "VDDE_IOA_G5") (pintype "power_in"))
      (node (ref "U6") (pin "H5") (pinfunction "VDDE_IOA_H5") (pintype "power_in"))
      (node (ref "U6") (pin "K11") (pinfunction "VDDE_IOC_K11") (pintype "power_in"))
      (node (ref "U6") (pin "L10") (pinfunction "VDDE_IOC_L10") (pintype "power_in"))
      (node (ref "U6") (pin "L4") (pinfunction "VDDE_IOB_L4") (pintype "power_in"))
      (node (ref "U6") (pin "M5") (pinfunction "VDDE_IOB_M5") (pintype "power_in"))
      (node (ref "U6") (pin "M7") (pinfunction "VDDE_IOB_M7") (pintype "power_in"))
      (node (ref "U6") (pin "M9") (pinfunction "VDDE_IOB_M9") (pintype "power_in"))
      (node (ref "U6") (pin "P1") (pinfunction "USB_VDDA33_P1") (pintype "power_in"))
    )
  )
)
